# InstrumentationAmp.net
KiCad netlist of a schematic drawn in EAGLE
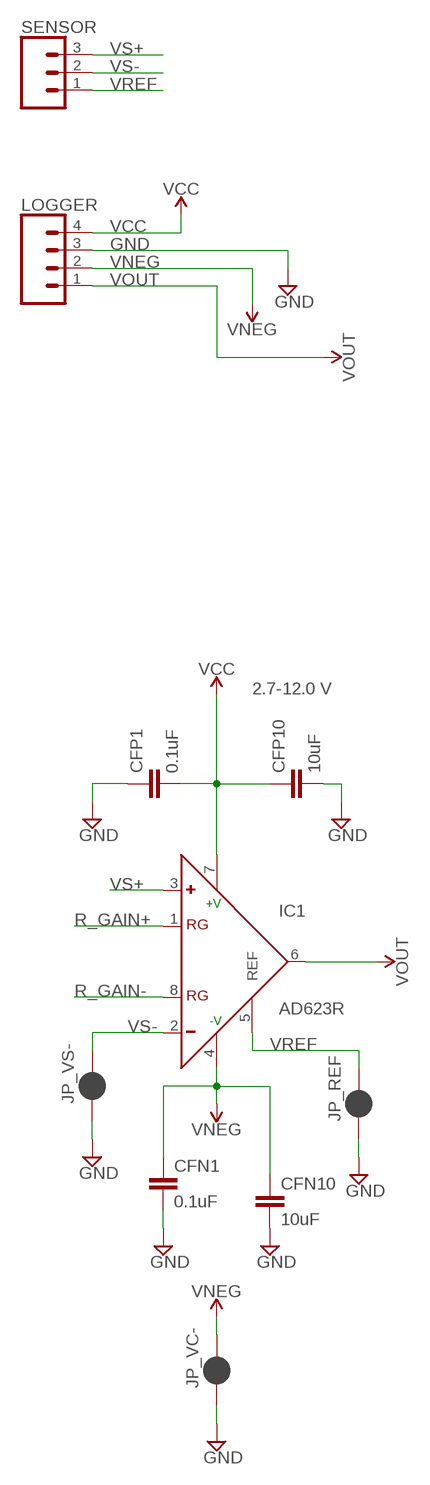
[diagram p0: schematic, sheet 1]
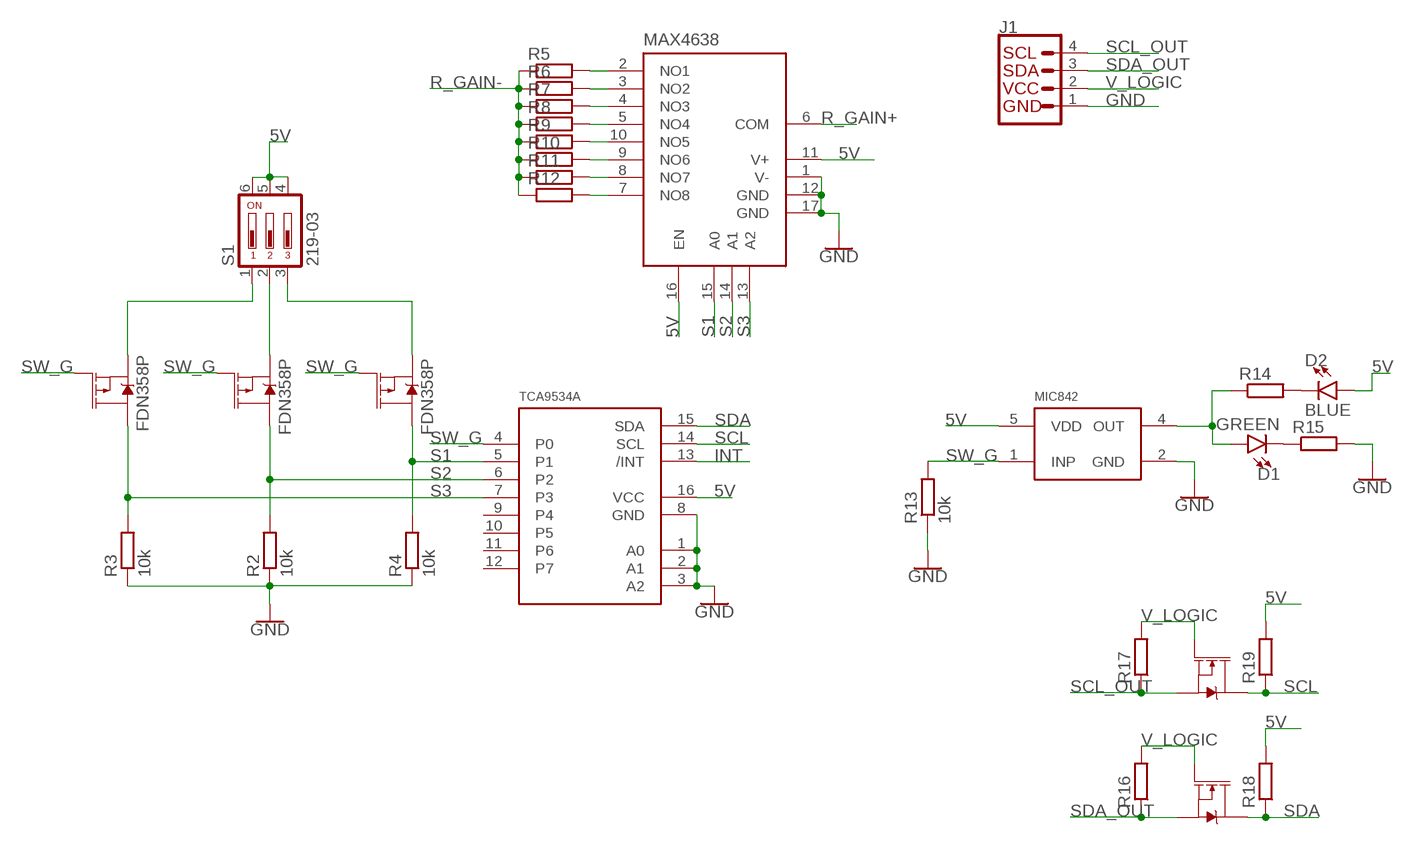
[diagram p1: schematic, sheet 2]
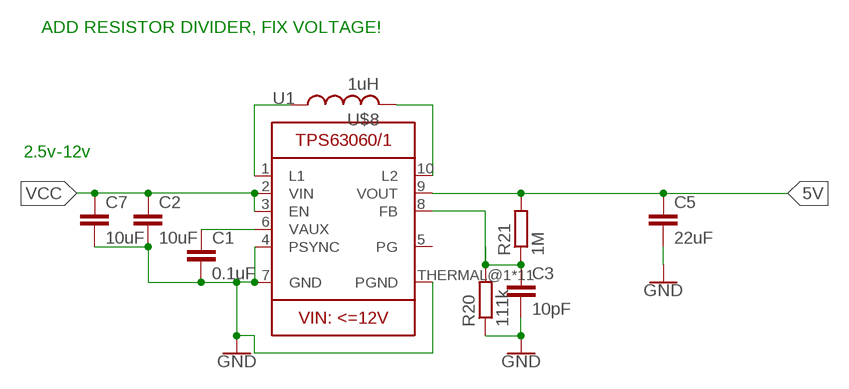
[diagram p2: schematic, sheet 3]

(export (version "E")
  (design (tool "Eeschema 10.0.6"))
  (components
    (comp (ref "C1")
      (value "0.1uF")
      (footprint "eagle-import:C0603")
      (libsource (lib "eagle-import") (part "rcl_C-EUC0603"))
    )
    (comp (ref "C2")
      (value "10uF")
      (footprint "eagle-import:C0805")
      (fields (field (name "MF") "Samsung") (field (name "MPN") "CL21A106KQCLRNC"))
      (libsource (lib "eagle-import") (part "C-EUC080510UF"))
    )
    (comp (ref "C3")
      (value "10pF")
      (footprint "eagle-import:C0603")
      (libsource (lib "eagle-import") (part "rcl_C-EUC0603"))
    )
    (comp (ref "C5")
      (value "22uF")
      (footprint "eagle-import:C0805")
      (fields (field (name "MF") "Samsung") (field (name "MPN") "CL21A226KQCLRNC"))
      (libsource (lib "eagle-import") (part "C-EUC080522UF"))
    )
    (comp (ref "C7")
      (value "10uF")
      (footprint "eagle-import:C0805")
      (fields (field (name "MF") "Samsung") (field (name "MPN") "CL21A106KQCLRNC"))
      (libsource (lib "eagle-import") (part "C-EUC080510UF"))
    )
    (comp (ref "R20")
      (value "111k")
      (footprint "eagle-import:R0603")
      (libsource (lib "eagle-import") (part "R-EU_R0603"))
    )
    (comp (ref "R21")
      (value "1M")
      (footprint "eagle-import:R0603")
      (libsource (lib "eagle-import") (part "R-EU_R0603"))
    )
    (comp (ref "U$8")
      (value "1uH")
      (footprint "eagle-import:WE-MAIA(4.1X4.1)")
      (libsource (lib "eagle-import") (part "WE-MAIA(INDUCTOR)"))
    )
    (comp (ref "U1")
      (value "TPS63061")
      (footprint "eagle-import:PWSON-N10")
      (fields (field (name "MF") "TI") (field (name "MPN") "TPS63061DSCR"))
      (libsource (lib "eagle-import") (part "TPS63061"))
    )
    (comp (ref "CFN1")
      (value "0.1uF")
      (footprint "eagle-import:0603")
      (libsource (lib "eagle-import") (part "0.1UF-0603-25V-(+80/-20%)"))
    )
    (comp (ref "CFN10")
      (value "10uF")
      (footprint "eagle-import:C0805")
      (libsource (lib "eagle-import") (part "C-EUC0805"))
    )
    (comp (ref "CFP1")
      (value "0.1uF")
      (footprint "eagle-import:0603")
      (libsource (lib "eagle-import") (part "0.1UF-0603-25V-(+80/-20%)"))
    )
    (comp (ref "CFP10")
      (value "10uF")
      (footprint "eagle-import:C0805")
      (libsource (lib "eagle-import") (part "C-EUC0805"))
    )
    (comp (ref "IC1")
      (value "AD623R")
      (footprint "eagle-import:SO8")
      (fields (field (name "MPN") "AD623ARZ."))
      (libsource (lib "eagle-import") (part "AD623R"))
    )
    (comp (ref "JP_REF")
      (value "JUMPER-SMT_2_NC_PASTE_SILK")
      (footprint "eagle-import:SMT-JUMPER_2_NC_PASTE_SILK")
      (libsource (lib "eagle-import") (part "JUMPER-SMT_2_NC_PASTE_SILK"))
    )
    (comp (ref "JP_VC-")
      (value "JUMPER-SMT_2_NC_PASTE_SILK")
      (footprint "eagle-import:SMT-JUMPER_2_NC_PASTE_SILK")
      (libsource (lib "eagle-import") (part "JUMPER-SMT_2_NC_PASTE_SILK"))
    )
    (comp (ref "JP_VS-")
      (value "JUMPER-SMT_2_NC_PASTE_SILK")
      (footprint "eagle-import:SMT-JUMPER_2_NC_PASTE_SILK")
      (libsource (lib "eagle-import") (part "JUMPER-SMT_2_NC_PASTE_SILK"))
    )
    (comp (ref "LOGGER")
      (value "CONN_04")
      (footprint "eagle-import:1X04")
      (libsource (lib "eagle-import") (part "CONN_04"))
    )
    (comp (ref "SENSOR")
      (value "CONN_03")
      (footprint "eagle-import:1X03")
      (libsource (lib "eagle-import") (part "CONN_03"))
    )
    (comp (ref "D1")
      (value "GREEN")
      (footprint "eagle-import:LED-0603")
      (libsource (lib "eagle-import") (part "LED-GREEN0603"))
    )
    (comp (ref "D2")
      (value "BLUE")
      (footprint "eagle-import:LED-0603")
      (libsource (lib "eagle-import") (part "LED-BLUE0603"))
    )
    (comp (ref "J1")
      (value "I2C_STANDARD")
      (footprint "eagle-import:1X04")
      (libsource (lib "eagle-import") (part "I2C_STANDARD"))
    )
    (comp (ref "Q1")
      (value "310mA/60V/1.6Ω")
      (footprint "eagle-import:SOT323")
      (libsource (lib "eagle-import") (part "MOSFET-NCH-2N7002PW"))
    )
    (comp (ref "Q2")
      (value "310mA/60V/1.6Ω")
      (footprint "eagle-import:SOT323")
      (libsource (lib "eagle-import") (part "MOSFET-NCH-2N7002PW"))
    )
    (comp (ref "R2")
      (value "10k")
      (footprint "eagle-import:R0603")
      (libsource (lib "eagle-import") (part "R-EU_R0603"))
    )
    (comp (ref "R3")
      (value "10k")
      (footprint "eagle-import:R0603")
      (libsource (lib "eagle-import") (part "R-EU_R0603"))
    )
    (comp (ref "R4")
      (value "10k")
      (footprint "eagle-import:R0603")
      (libsource (lib "eagle-import") (part "R-EU_R0603"))
    )
    (comp (ref "R5")
      (value "R-EU_R0603")
      (footprint "eagle-import:R0603")
      (libsource (lib "eagle-import") (part "R-EU_R0603"))
    )
    (comp (ref "R6")
      (value "R-EU_R0603")
      (footprint "eagle-import:R0603")
      (libsource (lib "eagle-import") (part "R-EU_R0603"))
    )
    (comp (ref "R7")
      (value "R-EU_R0603")
      (footprint "eagle-import:R0603")
      (libsource (lib "eagle-import") (part "R-EU_R0603"))
    )
    (comp (ref "R8")
      (value "R-EU_R0603")
      (footprint "eagle-import:R0603")
      (libsource (lib "eagle-import") (part "R-EU_R0603"))
    )
    (comp (ref "R9")
      (value "R-EU_R0603")
      (footprint "eagle-import:R0603")
      (libsource (lib "eagle-import") (part "R-EU_R0603"))
    )
    (comp (ref "R10")
      (value "R-EU_R0603")
      (footprint "eagle-import:R0603")
      (libsource (lib "eagle-import") (part "R-EU_R0603"))
    )
    (comp (ref "R11")
      (value "R-EU_R0603")
      (footprint "eagle-import:R0603")
      (libsource (lib "eagle-import") (part "R-EU_R0603"))
    )
    (comp (ref "R12")
      (value "R-EU_R0603")
      (footprint "eagle-import:R0603")
      (libsource (lib "eagle-import") (part "R-EU_R0603"))
    )
    (comp (ref "R13")
      (value "10k")
      (footprint "eagle-import:R0603")
      (libsource (lib "eagle-import") (part "R-EU_R0603"))
    )
    (comp (ref "R14")
      (value "R-EU_R0603")
      (footprint "eagle-import:R0603")
      (libsource (lib "eagle-import") (part "R-EU_R0603"))
    )
    (comp (ref "R15")
      (value "R-EU_R0603")
      (footprint "eagle-import:R0603")
      (libsource (lib "eagle-import") (part "R-EU_R0603"))
    )
    (comp (ref "R16")
      (value "R-EU_R0603")
      (footprint "eagle-import:R0603")
      (libsource (lib "eagle-import") (part "R-EU_R0603"))
    )
    (comp (ref "R17")
      (value "R-EU_R0603")
      (footprint "eagle-import:R0603")
      (libsource (lib "eagle-import") (part "R-EU_R0603"))
    )
    (comp (ref "R18")
      (value "R-EU_R0603")
      (footprint "eagle-import:R0603")
      (libsource (lib "eagle-import") (part "R-EU_R0603"))
    )
    (comp (ref "R19")
      (value "R-EU_R0603")
      (footprint "eagle-import:R0603")
      (libsource (lib "eagle-import") (part "R-EU_R0603"))
    )
    (comp (ref "S1")
      (value "219-03")
      (footprint "eagle-import:CTS-219-03")
      (libsource (lib "eagle-import") (part "219-03"))
    )
    (comp (ref "U$1")
      (value "MAX4638")
      (footprint "eagle-import:TQFN16")
      (libsource (lib "eagle-import") (part "MAX4638"))
    )
    (comp (ref "U$2")
      (value "TCA9534A")
      (footprint "eagle-import:TSSOP16")
      (libsource (lib "eagle-import") (part "TCA9534A"))
    )
    (comp (ref "U$3")
      (value "FDN358P")
      (footprint "eagle-import:SSOT-3")
      (libsource (lib "eagle-import") (part "FDN358P"))
    )
    (comp (ref "U$4")
      (value "FDN358P")
      (footprint "eagle-import:SSOT-3")
      (libsource (lib "eagle-import") (part "FDN358P"))
    )
    (comp (ref "U$5")
      (value "FDN358P")
      (footprint "eagle-import:SSOT-3")
      (libsource (lib "eagle-import") (part "FDN358P"))
    )
    (comp (ref "U$6")
      (value "MIC842")
      (footprint "eagle-import:DCK_R-PDSO-G5")
      (libsource (lib "eagle-import") (part "MIC842"))
    )
  )
  (nets
    (net (code "1") (name "5V") (class "Default")
      (node (ref "C5") (pin "1") (pinfunction "1_1") (pintype "passive"))
      (node (ref "D2") (pin "A") (pinfunction "A_A") (pintype "passive"))
      (node (ref "R18") (pin "2") (pinfunction "2_2") (pintype "passive"))
      (node (ref "R19") (pin "2") (pinfunction "2_2") (pintype "passive"))
      (node (ref "R21") (pin "2") (pinfunction "2_2") (pintype "passive"))
      (node (ref "S1") (pin "4") (pinfunction "4_4") (pintype "passive"))
      (node (ref "S1") (pin "5") (pinfunction "5_5") (pintype "passive"))
      (node (ref "S1") (pin "6") (pinfunction "6_6") (pintype "passive"))
      (node (ref "U$1") (pin "11") (pinfunction "V+_11") (pintype "power_in"))
      (node (ref "U$1") (pin "16") (pinfunction "EN_16") (pintype "input"))
      (node (ref "U$2") (pin "16") (pinfunction "VCC_16") (pintype "power_in"))
      (node (ref "U$6") (pin "5") (pinfunction "VDD_5") (pintype "power_in"))
      (node (ref "U1") (pin "9") (pinfunction "VOUT_9") (pintype "power_in"))
    )
    (net (code "2") (name "GND") (class "Default")
      (node (ref "C1") (pin "2") (pinfunction "2_2") (pintype "passive"))
      (node (ref "C2") (pin "2") (pinfunction "2_2") (pintype "passive"))
      (node (ref "C3") (pin "2") (pinfunction "2_2") (pintype "passive"))
      (node (ref "C5") (pin "2") (pinfunction "2_2") (pintype "passive"))
      (node (ref "C7") (pin "2") (pinfunction "2_2") (pintype "passive"))
      (node (ref "CFN1") (pin "2") (pinfunction "2_2") (pintype "passive"))
      (node (ref "CFN10") (pin "2") (pinfunction "2_2") (pintype "passive"))
      (node (ref "CFP1") (pin "1") (pinfunction "1_1") (pintype "passive"))
      (node (ref "CFP10") (pin "2") (pinfunction "2_2") (pintype "passive"))
      (node (ref "J1") (pin "1") (pinfunction "1_1") (pintype "power_in"))
      (node (ref "JP_REF") (pin "1") (pinfunction "1_1") (pintype "passive"))
      (node (ref "JP_VC-") (pin "1") (pinfunction "1_1") (pintype "passive"))
      (node (ref "JP_VS-") (pin "1") (pinfunction "1_1") (pintype "passive"))
      (node (ref "LOGGER") (pin "3") (pinfunction "3_3") (pintype "passive"))
      (node (ref "R13") (pin "1") (pinfunction "1_1") (pintype "passive"))
      (node (ref "R15") (pin "2") (pinfunction "2_2") (pintype "passive"))
      (node (ref "R2") (pin "1") (pinfunction "1_1") (pintype "passive"))
      (node (ref "R20") (pin "1") (pinfunction "1_1") (pintype "passive"))
      (node (ref "R3") (pin "1") (pinfunction "1_1") (pintype "passive"))
      (node (ref "R4") (pin "1") (pinfunction "1_1") (pintype "passive"))
      (node (ref "U$1") (pin "1") (pinfunction "V-_1") (pintype "power_in"))
      (node (ref "U$1") (pin "12") (pinfunction "GND_12") (pintype "power_in"))
      (node (ref "U$1") (pin "17") (pinfunction "GND_17") (pintype "power_in"))
      (node (ref "U$2") (pin "1") (pinfunction "A0_1") (pintype "input"))
      (node (ref "U$2") (pin "2") (pinfunction "A1_2") (pintype "input"))
      (node (ref "U$2") (pin "3") (pinfunction "A2_3") (pintype "input"))
      (node (ref "U$2") (pin "8") (pinfunction "GND_8") (pintype "power_in"))
      (node (ref "U$6") (pin "2") (pinfunction "GND_2") (pintype "power_in"))
      (node (ref "U1") (pin "4") (pinfunction "PSYNC_4") (pintype "input"))
      (node (ref "U1") (pin "7") (pinfunction "GND_7") (pintype "power_in"))
      (node (ref "U1") (pin "THERMAL@1") (pinfunction "PGND_THERMAL@1") (pintype "power_in"))
      (node (ref "U1") (pin "THERMAL@10") (pinfunction "PGND_THERMAL@10") (pintype "power_in"))
      (node (ref "U1") (pin "THERMAL@11") (pinfunction "PGND_THERMAL@11") (pintype "power_in"))
      (node (ref "U1") (pin "THERMAL@12") (pinfunction "PGND_THERMAL@12") (pintype "power_in"))
      (node (ref "U1") (pin "THERMAL@13") (pinfunction "PGND_THERMAL@13") (pintype "power_in"))
      (node (ref "U1") (pin "THERMAL@14") (pinfunction "PGND_THERMAL@14") (pintype "power_in"))
      (node (ref "U1") (pin "THERMAL@5") (pinfunction "PGND_THERMAL@5") (pintype "power_in"))
      (node (ref "U1") (pin "THERMAL@6") (pinfunction "PGND_THERMAL@6") (pintype "power_in"))
      (node (ref "U1") (pin "THERMAL@7") (pinfunction "PGND_THERMAL@7") (pintype "power_in"))
      (node (ref "U1") (pin "THERMAL@8") (pinfunction "PGND_THERMAL@8") (pintype "power_in"))
      (node (ref "U1") (pin "THERMAL@9") (pinfunction "PGND_THERMAL@9") (pintype "power_in"))
    )
    (net (code "3") (name "INT") (class "Default")
      (node (ref "U$2") (pin "13") (pinfunction "/INT_13") (pintype "output"))
    )
    (net (code "4") (name "Net-(D1-PadC)") (class "Default")
      (node (ref "D1") (pin "C") (pinfunction "C_C") (pintype "passive"))
      (node (ref "R15") (pin "1") (pinfunction "1_1") (pintype "passive"))
    )
    (net (code "5") (name "Net-(D2-PadC)") (class "Default")
      (node (ref "D2") (pin "C") (pinfunction "C_C") (pintype "passive"))
      (node (ref "R14") (pin "2") (pinfunction "2_2") (pintype "passive"))
    )
    (net (code "6") (name "Net-(U$1-NO1)") (class "Default")
      (node (ref "R5") (pin "2") (pinfunction "2_2") (pintype "passive"))
      (node (ref "U$1") (pin "2") (pinfunction "NO1_2") (pintype "bidirectional"))
    )
    (net (code "7") (name "Net-(U$1-NO2)") (class "Default")
      (node (ref "R6") (pin "2") (pinfunction "2_2") (pintype "passive"))
      (node (ref "U$1") (pin "3") (pinfunction "NO2_3") (pintype "bidirectional"))
    )
    (net (code "8") (name "Net-(U$1-NO3)") (class "Default")
      (node (ref "R7") (pin "2") (pinfunction "2_2") (pintype "passive"))
      (node (ref "U$1") (pin "4") (pinfunction "NO3_4") (pintype "bidirectional"))
    )
    (net (code "9") (name "Net-(U$1-NO4)") (class "Default")
      (node (ref "R8") (pin "2") (pinfunction "2_2") (pintype "passive"))
      (node (ref "U$1") (pin "5") (pinfunction "NO4_5") (pintype "bidirectional"))
    )
    (net (code "10") (name "Net-(U$1-NO5)") (class "Default")
      (node (ref "R9") (pin "2") (pinfunction "2_2") (pintype "passive"))
      (node (ref "U$1") (pin "10") (pinfunction "NO5_10") (pintype "bidirectional"))
    )
    (net (code "11") (name "Net-(U$1-NO6)") (class "Default")
      (node (ref "R10") (pin "2") (pinfunction "2_2") (pintype "passive"))
      (node (ref "U$1") (pin "9") (pinfunction "NO6_9") (pintype "bidirectional"))
    )
    (net (code "12") (name "Net-(U$1-NO7)") (class "Default")
      (node (ref "R11") (pin "2") (pinfunction "2_2") (pintype "passive"))
      (node (ref "U$1") (pin "8") (pinfunction "NO7_8") (pintype "bidirectional"))
    )
    (net (code "13") (name "Net-(U$1-NO8)") (class "Default")
      (node (ref "R12") (pin "2") (pinfunction "2_2") (pintype "passive"))
      (node (ref "U$1") (pin "7") (pinfunction "NO8_7") (pintype "bidirectional"))
    )
    (net (code "14") (name "Net-(U$3-S)") (class "Default")
      (node (ref "S1") (pin "1") (pinfunction "1_1") (pintype "passive"))
      (node (ref "U$3") (pin "2") (pinfunction "S_2") (pintype "bidirectional"))
    )
    (net (code "15") (name "Net-(U$4-S)") (class "Default")
      (node (ref "S1") (pin "2") (pinfunction "2_2") (pintype "passive"))
      (node (ref "U$4") (pin "2") (pinfunction "S_2") (pintype "bidirectional"))
    )
    (net (code "16") (name "Net-(U$5-S)") (class "Default")
      (node (ref "S1") (pin "3") (pinfunction "3_3") (pintype "passive"))
      (node (ref "U$5") (pin "2") (pinfunction "S_2") (pintype "bidirectional"))
    )
    (net (code "17") (name "Net-(U$6-OUT)") (class "Default")
      (node (ref "D1") (pin "A") (pinfunction "A_A") (pintype "passive"))
      (node (ref "R14") (pin "1") (pinfunction "1_1") (pintype "passive"))
      (node (ref "U$6") (pin "4") (pinfunction "OUT_4") (pintype "output"))
    )
    (net (code "18") (name "Net-(U$8-1)") (class "Default")
      (node (ref "U$8") (pin "P$1") (pinfunction "1_P$1") (pintype "passive"))
      (node (ref "U1") (pin "1") (pinfunction "L1_1") (pintype "input"))
    )
    (net (code "19") (name "Net-(U$8-2)") (class "Default")
      (node (ref "U$8") (pin "P$2") (pinfunction "2_P$2") (pintype "passive"))
      (node (ref "U1") (pin "10") (pinfunction "L2_10") (pintype "input"))
    )
    (net (code "20") (name "Net-(U1-FB)") (class "Default")
      (node (ref "C3") (pin "1") (pinfunction "1_1") (pintype "passive"))
      (node (ref "R20") (pin "2") (pinfunction "2_2") (pintype "passive"))
      (node (ref "R21") (pin "1") (pinfunction "1_1") (pintype "passive"))
      (node (ref "U1") (pin "8") (pinfunction "FB_8") (pintype "input"))
    )
    (net (code "21") (name "Net-(U1-VAUX)") (class "Default")
      (node (ref "C1") (pin "1") (pinfunction "1_1") (pintype "passive"))
      (node (ref "U1") (pin "6") (pinfunction "VAUX_6") (pintype "passive"))
    )
    (net (code "22") (name "R_GAIN+") (class "Default")
      (node (ref "IC1") (pin "1") (pinfunction "RG_1") (pintype "passive"))
      (node (ref "U$1") (pin "6") (pinfunction "COM_6") (pintype "bidirectional"))
    )
    (net (code "23") (name "R_GAIN-") (class "Default")
      (node (ref "IC1") (pin "8") (pinfunction "RG_8") (pintype "passive"))
      (node (ref "R10") (pin "1") (pinfunction "1_1") (pintype "passive"))
      (node (ref "R11") (pin "1") (pinfunction "1_1") (pintype "passive"))
      (node (ref "R12") (pin "1") (pinfunction "1_1") (pintype "passive"))
      (node (ref "R5") (pin "1") (pinfunction "1_1") (pintype "passive"))
      (node (ref "R6") (pin "1") (pinfunction "1_1") (pintype "passive"))
      (node (ref "R7") (pin "1") (pinfunction "1_1") (pintype "passive"))
      (node (ref "R8") (pin "1") (pinfunction "1_1") (pintype "passive"))
      (node (ref "R9") (pin "1") (pinfunction "1_1") (pintype "passive"))
    )
    (net (code "24") (name "S1") (class "Default")
      (node (ref "R4") (pin "2") (pinfunction "2_2") (pintype "passive"))
      (node (ref "U$1") (pin "15") (pinfunction "A0_15") (pintype "input"))
      (node (ref "U$2") (pin "5") (pinfunction "P1_5") (pintype "bidirectional"))
      (node (ref "U$5") (pin "3") (pinfunction "D_3") (pintype "bidirectional"))
    )
    (net (code "25") (name "S2") (class "Default")
      (node (ref "R2") (pin "2") (pinfunction "2_2") (pintype "passive"))
      (node (ref "U$1") (pin "14") (pinfunction "A1_14") (pintype "input"))
      (node (ref "U$2") (pin "6") (pinfunction "P2_6") (pintype "bidirectional"))
      (node (ref "U$4") (pin "3") (pinfunction "D_3") (pintype "bidirectional"))
    )
    (net (code "26") (name "S3") (class "Default")
      (node (ref "R3") (pin "2") (pinfunction "2_2") (pintype "passive"))
      (node (ref "U$1") (pin "13") (pinfunction "A2_13") (pintype "input"))
      (node (ref "U$2") (pin "7") (pinfunction "P3_7") (pintype "bidirectional"))
      (node (ref "U$3") (pin "3") (pinfunction "D_3") (pintype "bidirectional"))
    )
    (net (code "27") (name "SCL") (class "Default")
      (node (ref "Q2") (pin "3") (pinfunction "D_3") (pintype "bidirectional"))
      (node (ref "R19") (pin "1") (pinfunction "1_1") (pintype "passive"))
      (node (ref "U$2") (pin "14") (pinfunction "SCL_14") (pintype "bidirectional"))
    )
    (net (code "28") (name "SCL_OUT") (class "Default")
      (node (ref "J1") (pin "4") (pinfunction "4_4") (pintype "passive"))
      (node (ref "Q2") (pin "2") (pinfunction "S_2") (pintype "bidirectional"))
      (node (ref "R17") (pin "1") (pinfunction "1_1") (pintype "passive"))
    )
    (net (code "29") (name "SDA") (class "Default")
      (node (ref "Q1") (pin "3") (pinfunction "D_3") (pintype "bidirectional"))
      (node (ref "R18") (pin "1") (pinfunction "1_1") (pintype "passive"))
      (node (ref "U$2") (pin "15") (pinfunction "SDA_15") (pintype "bidirectional"))
    )
    (net (code "30") (name "SDA_OUT") (class "Default")
      (node (ref "J1") (pin "3") (pinfunction "3_3") (pintype "passive"))
      (node (ref "Q1") (pin "2") (pinfunction "S_2") (pintype "bidirectional"))
      (node (ref "R16") (pin "1") (pinfunction "1_1") (pintype "passive"))
    )
    (net (code "31") (name "SW_G") (class "Default")
      (node (ref "R13") (pin "2") (pinfunction "2_2") (pintype "passive"))
      (node (ref "U$2") (pin "4") (pinfunction "P0_4") (pintype "bidirectional"))
      (node (ref "U$3") (pin "1") (pinfunction "G_1") (pintype "bidirectional"))
      (node (ref "U$4") (pin "1") (pinfunction "G_1") (pintype "bidirectional"))
      (node (ref "U$5") (pin "1") (pinfunction "G_1") (pintype "bidirectional"))
      (node (ref "U$6") (pin "1") (pinfunction "INP_1") (pintype "input"))
    )
    (net (code "32") (name "VCC") (class "Default")
      (node (ref "C2") (pin "1") (pinfunction "1_1") (pintype "passive"))
      (node (ref "C7") (pin "1") (pinfunction "1_1") (pintype "passive"))
      (node (ref "CFP1") (pin "2") (pinfunction "2_2") (pintype "passive"))
      (node (ref "CFP10") (pin "1") (pinfunction "1_1") (pintype "passive"))
      (node (ref "IC1") (pin "7") (pinfunction "+V_7") (pintype "power_in"))
      (node (ref "LOGGER") (pin "4") (pinfunction "4_4") (pintype "passive"))
      (node (ref "U1") (pin "2") (pinfunction "VIN_2") (pintype "power_in"))
      (node (ref "U1") (pin "3") (pinfunction "EN_3") (pintype "input"))
    )
    (net (code "33") (name "VNEG") (class "Default")
      (node (ref "CFN1") (pin "1") (pinfunction "1_1") (pintype "passive"))
      (node (ref "CFN10") (pin "1") (pinfunction "1_1") (pintype "passive"))
      (node (ref "IC1") (pin "4") (pinfunction "-V_4") (pintype "power_in"))
      (node (ref "JP_VC-") (pin "2") (pinfunction "2_2") (pintype "passive"))
      (node (ref "LOGGER") (pin "2") (pinfunction "2_2") (pintype "passive"))
    )
    (net (code "34") (name "VOUT") (class "Default")
      (node (ref "IC1") (pin "6") (pinfunction "OUT_6") (pintype "output"))
      (node (ref "LOGGER") (pin "1") (pinfunction "1_1") (pintype "passive"))
    )
    (net (code "35") (name "VREF") (class "Default")
      (node (ref "IC1") (pin "5") (pinfunction "REF_5") (pintype "passive"))
      (node (ref "JP_REF") (pin "2") (pinfunction "2_2") (pintype "passive"))
      (node (ref "SENSOR") (pin "1") (pinfunction "1_1") (pintype "passive"))
    )
    (net (code "36") (name "VS+") (class "Default")
      (node (ref "IC1") (pin "3") (pinfunction "+_3") (pintype "input"))
      (node (ref "SENSOR") (pin "3") (pinfunction "3_3") (pintype "passive"))
    )
    (net (code "37") (name "VS-") (class "Default")
      (node (ref "IC1") (pin "2") (pinfunction "-_2") (pintype "input"))
      (node (ref "JP_VS-") (pin "2") (pinfunction "2_2") (pintype "passive"))
      (node (ref "SENSOR") (pin "2") (pinfunction "2_2") (pintype "passive"))
    )
    (net (code "38") (name "V_LOGIC") (class "Default")
      (node (ref "J1") (pin "2") (pinfunction "2_2") (pintype "power_in"))
      (node (ref "Q1") (pin "1") (pinfunction "G_1") (pintype "bidirectional"))
      (node (ref "Q2") (pin "1") (pinfunction "G_1") (pintype "bidirectional"))
      (node (ref "R16") (pin "2") (pinfunction "2_2") (pintype "passive"))
      (node (ref "R17") (pin "2") (pinfunction "2_2") (pintype "passive"))
    )
    (net (code "39") (name "unconnected-(U$2-P4-Pad9)") (class "Default")
      (node (ref "U$2") (pin "9") (pinfunction "P4_9") (pintype "bidirectional"))
    )
    (net (code "40") (name "unconnected-(U$2-P5-Pad10)") (class "Default")
      (node (ref "U$2") (pin "10") (pinfunction "P5_10") (pintype "bidirectional"))
    )
    (net (code "41") (name "unconnected-(U$2-P6-Pad11)") (class "Default")
      (node (ref "U$2") (pin "11") (pinfunction "P6_11") (pintype "bidirectional"))
    )
    (net (code "42") (name "unconnected-(U$2-P7-Pad12)") (class "Default")
      (node (ref "U$2") (pin "12") (pinfunction "P7_12") (pintype "bidirectional"))
    )
    (net (code "43") (name "unconnected-(U1-PG-Pad5)") (class "Default")
      (node (ref "U1") (pin "5") (pinfunction "PG_5") (pintype "open_collector"))
    )
  )
)
